# main.net
KiCad netlist of a schematic drawn in EAGLE
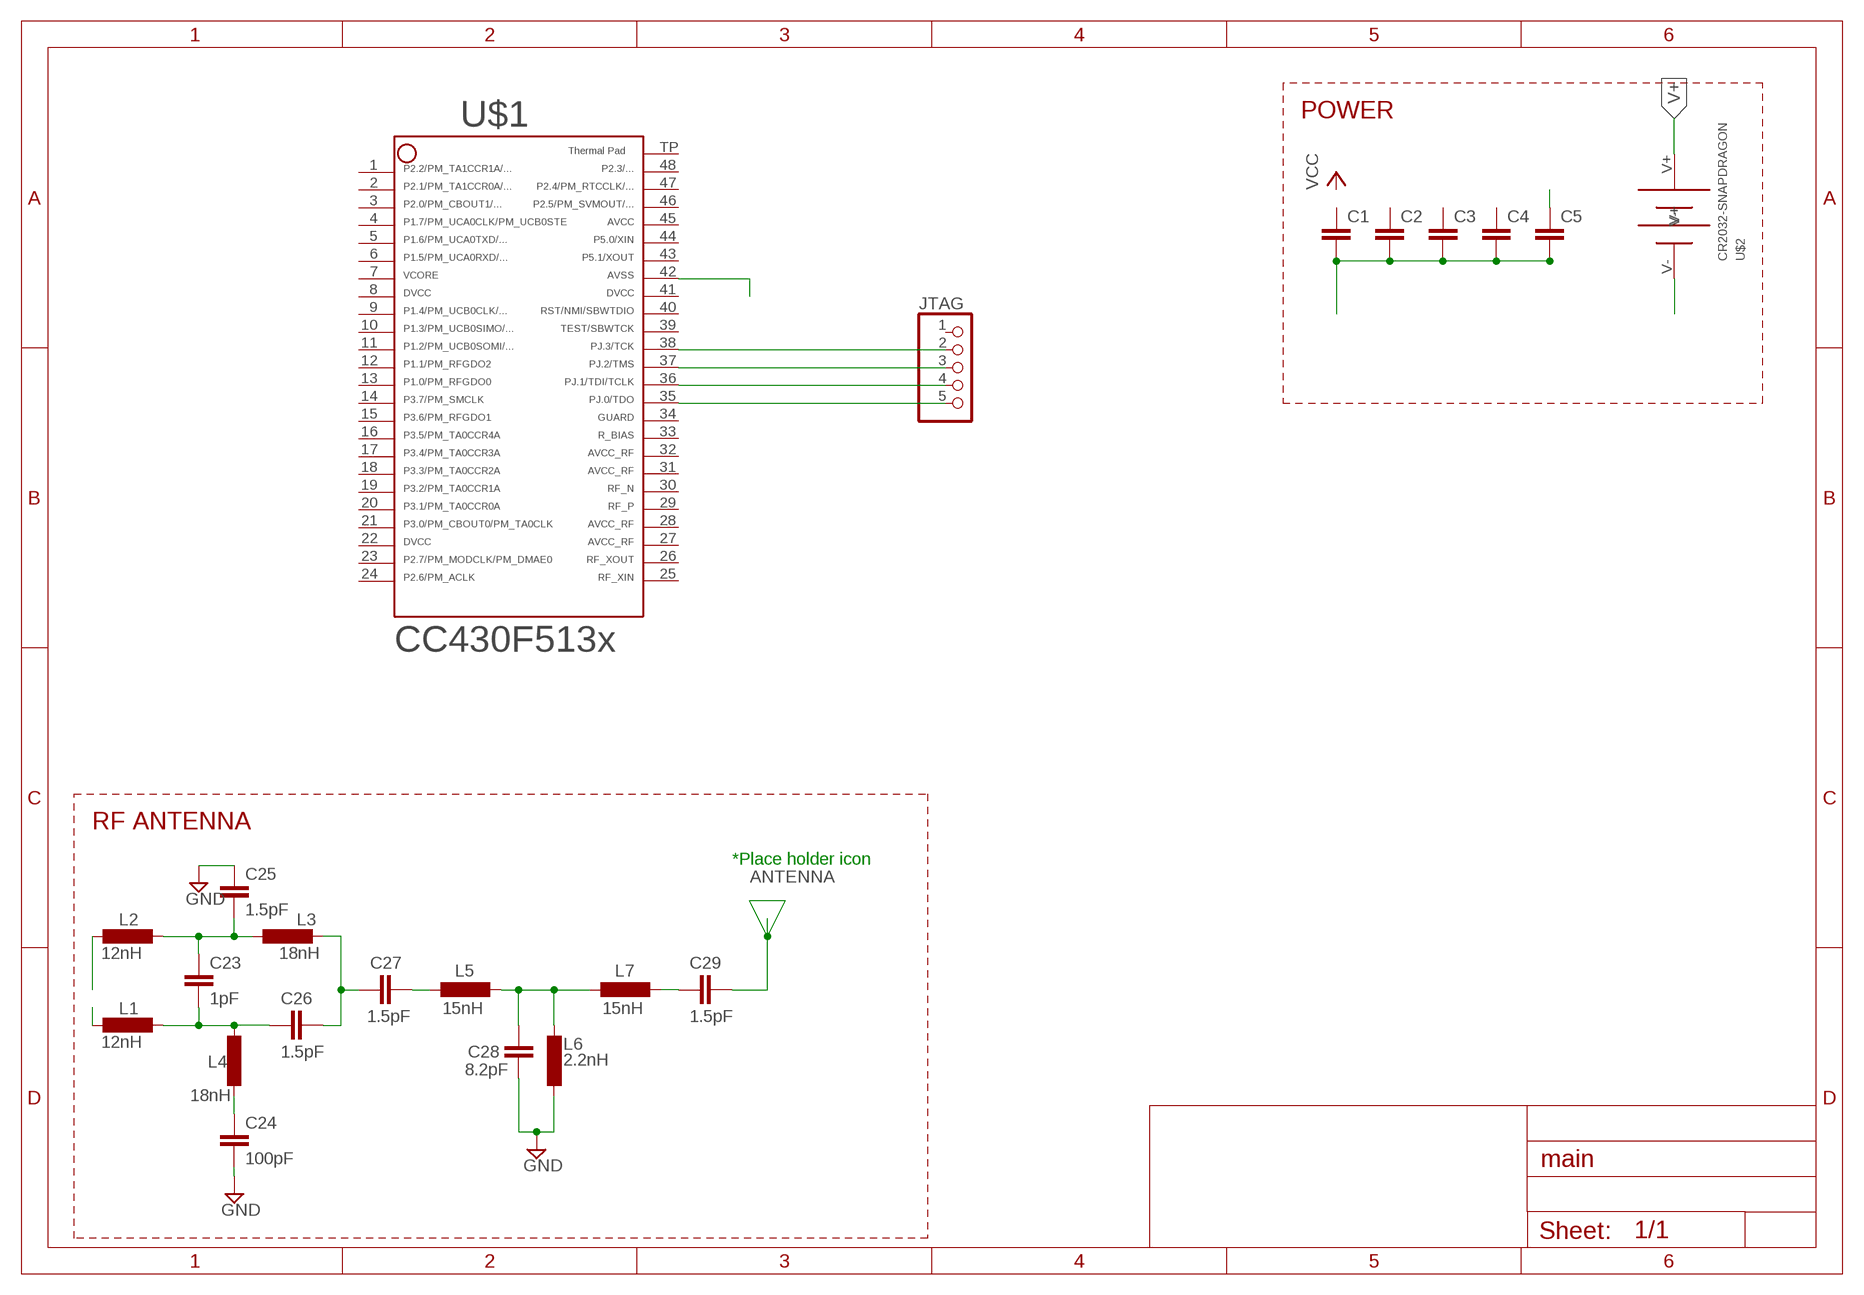
[diagram p0: schematic, sheet 1]

(export (version "E")
  (design (tool "Eeschema 10.0.6"))
  (components
    (comp (ref "C1")
      (value "C-EUC0603")
      (footprint "eagle-import:C0603")
      (libsource (lib "eagle-import") (part "C-EUC0603"))
    )
    (comp (ref "C2")
      (value "C-EUC0603")
      (footprint "eagle-import:C0603")
      (libsource (lib "eagle-import") (part "C-EUC0603"))
    )
    (comp (ref "C3")
      (value "C-EUC0603")
      (footprint "eagle-import:C0603")
      (libsource (lib "eagle-import") (part "C-EUC0603"))
    )
    (comp (ref "C4")
      (value "C-EUC0603")
      (footprint "eagle-import:C0603")
      (libsource (lib "eagle-import") (part "C-EUC0603"))
    )
    (comp (ref "C5")
      (value "C-EUC0603")
      (footprint "eagle-import:C0603")
      (libsource (lib "eagle-import") (part "C-EUC0603"))
    )
    (comp (ref "C23")
      (value "1pF")
      (footprint "eagle-import:C0603")
      (libsource (lib "eagle-import") (part "C-EUC0603"))
    )
    (comp (ref "C24")
      (value "100pF")
      (footprint "eagle-import:C0603")
      (libsource (lib "eagle-import") (part "C-EUC0603"))
    )
    (comp (ref "C25")
      (value "1.5pF")
      (footprint "eagle-import:C0603")
      (libsource (lib "eagle-import") (part "C-EUC0603"))
    )
    (comp (ref "C26")
      (value "1.5pF")
      (footprint "eagle-import:C0603")
      (libsource (lib "eagle-import") (part "C-EUC0603"))
    )
    (comp (ref "C27")
      (value "1.5pF")
      (footprint "eagle-import:C0603")
      (libsource (lib "eagle-import") (part "C-EUC0603"))
    )
    (comp (ref "C28")
      (value "8.2pF")
      (footprint "eagle-import:C0603")
      (libsource (lib "eagle-import") (part "C-EUC0603"))
    )
    (comp (ref "C29")
      (value "1.5pF")
      (footprint "eagle-import:C0603")
      (libsource (lib "eagle-import") (part "C-EUC0603"))
    )
    (comp (ref "JTAG")
      (value "PINHD-1X5")
      (footprint "eagle-import:1X05")
      (libsource (lib "eagle-import") (part "PINHD-1X5"))
    )
    (comp (ref "L1")
      (value "12nH")
      (footprint "eagle-import:L0603")
      (libsource (lib "eagle-import") (part "LL0603"))
    )
    (comp (ref "L2")
      (value "12nH")
      (footprint "eagle-import:L0603")
      (libsource (lib "eagle-import") (part "LL0603"))
    )
    (comp (ref "L3")
      (value "18nH")
      (footprint "eagle-import:L0603")
      (libsource (lib "eagle-import") (part "LL0603"))
    )
    (comp (ref "L4")
      (value "18nH")
      (footprint "eagle-import:L0603")
      (libsource (lib "eagle-import") (part "LL0603"))
    )
    (comp (ref "L5")
      (value "15nH")
      (footprint "eagle-import:L0603")
      (libsource (lib "eagle-import") (part "LL0603"))
    )
    (comp (ref "L6")
      (value "2.2nH")
      (footprint "eagle-import:L0603")
      (libsource (lib "eagle-import") (part "LL0603"))
    )
    (comp (ref "L7")
      (value "15nH")
      (footprint "eagle-import:L0603")
      (libsource (lib "eagle-import") (part "LL0603"))
    )
    (comp (ref "U$1")
      (value "CC430F513X---RGZ48")
      (footprint "eagle-import:RGZ48")
      (libsource (lib "eagle-import") (part "CC430F513X---RGZ48"))
    )
    (comp (ref "U$2")
      (value "CR2032-SNAPDRAGON")
      (footprint "eagle-import:CR2032-SNAPDRAGON")
      (libsource (lib "eagle-import") (part "CR2032-SNAPDRAGON"))
    )
  )
  (nets
    (net (code "1") (name "/7") (class "Default")
      (node (ref "U$1") (pin "7") (pinfunction "7_7") (pintype "power_in"))
    )
    (net (code "2") (name "/8") (class "Default")
      (node (ref "U$1") (pin "8") (pinfunction "8_8") (pintype "power_in"))
    )
    (net (code "3") (name "/22") (class "Default")
      (node (ref "U$1") (pin "22") (pinfunction "22_22") (pintype "power_in"))
    )
    (net (code "4") (name "/27") (class "Default")
      (node (ref "U$1") (pin "27") (pinfunction "27_27") (pintype "power_in"))
    )
    (net (code "5") (name "/31") (class "Default")
      (node (ref "U$1") (pin "31") (pinfunction "31_31") (pintype "power_in"))
    )
    (net (code "6") (name "/32") (class "Default")
      (node (ref "U$1") (pin "32") (pinfunction "32_32") (pintype "power_in"))
    )
    (net (code "7") (name "/33") (class "Default")
      (node (ref "U$1") (pin "33") (pinfunction "33_33") (pintype "power_in"))
    )
    (net (code "8") (name "/34") (class "Default")
      (node (ref "U$1") (pin "34") (pinfunction "34_34") (pintype "power_in"))
    )
    (net (code "9") (name "/41") (class "Default")
      (node (ref "U$1") (pin "41") (pinfunction "41_41") (pintype "power_in"))
    )
    (net (code "10") (name "/49") (class "Default")
      (node (ref "U$1") (pin "TP") (pinfunction "49_TP") (pintype "power_in"))
    )
    (net (code "11") (name "/ANTENNA") (class "Default")
      (node (ref "C29") (pin "1") (pinfunction "1_1") (pintype "passive"))
    )
    (net (code "12") (name "GND") (class "Default")
      (node (ref "C24") (pin "2") (pinfunction "2_2") (pintype "passive"))
      (node (ref "C25") (pin "1") (pinfunction "1_1") (pintype "passive"))
      (node (ref "C28") (pin "1") (pinfunction "1_1") (pintype "passive"))
      (node (ref "L6") (pin "2") (pinfunction "2_2") (pintype "passive"))
      (node (ref "U$2") (pin "V-") (pinfunction "V-_V-") (pintype "bidirectional"))
    )
    (net (code "13") (name "Net-(C1-Pad2)") (class "Default")
      (node (ref "C1") (pin "2") (pinfunction "2_2") (pintype "passive"))
      (node (ref "C2") (pin "2") (pinfunction "2_2") (pintype "passive"))
      (node (ref "C3") (pin "2") (pinfunction "2_2") (pintype "passive"))
      (node (ref "C4") (pin "2") (pinfunction "2_2") (pintype "passive"))
      (node (ref "C5") (pin "2") (pinfunction "2_2") (pintype "passive"))
    )
    (net (code "14") (name "Net-(C23-Pad1)") (class "Default")
      (node (ref "C23") (pin "1") (pinfunction "1_1") (pintype "passive"))
      (node (ref "C25") (pin "2") (pinfunction "2_2") (pintype "passive"))
      (node (ref "L2") (pin "1") (pinfunction "1_1") (pintype "passive"))
      (node (ref "L3") (pin "2") (pinfunction "2_2") (pintype "passive"))
    )
    (net (code "15") (name "Net-(C23-Pad2)") (class "Default")
      (node (ref "C23") (pin "2") (pinfunction "2_2") (pintype "passive"))
      (node (ref "C26") (pin "2") (pinfunction "2_2") (pintype "passive"))
      (node (ref "L1") (pin "1") (pinfunction "1_1") (pintype "passive"))
      (node (ref "L4") (pin "1") (pinfunction "1_1") (pintype "passive"))
    )
    (net (code "16") (name "Net-(C24-Pad1)") (class "Default")
      (node (ref "C24") (pin "1") (pinfunction "1_1") (pintype "passive"))
      (node (ref "L4") (pin "2") (pinfunction "2_2") (pintype "passive"))
    )
    (net (code "17") (name "Net-(C26-Pad1)") (class "Default")
      (node (ref "C26") (pin "1") (pinfunction "1_1") (pintype "passive"))
      (node (ref "C27") (pin "1") (pinfunction "1_1") (pintype "passive"))
      (node (ref "L3") (pin "1") (pinfunction "1_1") (pintype "passive"))
    )
    (net (code "18") (name "Net-(C27-Pad2)") (class "Default")
      (node (ref "C27") (pin "2") (pinfunction "2_2") (pintype "passive"))
      (node (ref "L5") (pin "1") (pinfunction "1_1") (pintype "passive"))
    )
    (net (code "19") (name "Net-(C28-Pad2)") (class "Default")
      (node (ref "C28") (pin "2") (pinfunction "2_2") (pintype "passive"))
      (node (ref "L5") (pin "2") (pinfunction "2_2") (pintype "passive"))
      (node (ref "L6") (pin "1") (pinfunction "1_1") (pintype "passive"))
      (node (ref "L7") (pin "1") (pinfunction "1_1") (pintype "passive"))
    )
    (net (code "20") (name "Net-(C29-Pad2)") (class "Default")
      (node (ref "C29") (pin "2") (pinfunction "2_2") (pintype "passive"))
      (node (ref "L7") (pin "2") (pinfunction "2_2") (pintype "passive"))
    )
    (net (code "21") (name "Net-(JTAG-Pad2)") (class "Default")
      (node (ref "JTAG") (pin "2") (pinfunction "2_2") (pintype "passive"))
      (node (ref "U$1") (pin "38") (pinfunction "38_38") (pintype "bidirectional"))
    )
    (net (code "22") (name "Net-(JTAG-Pad3)") (class "Default")
      (node (ref "JTAG") (pin "3") (pinfunction "3_3") (pintype "passive"))
      (node (ref "U$1") (pin "37") (pinfunction "37_37") (pintype "bidirectional"))
    )
    (net (code "23") (name "Net-(JTAG-Pad4)") (class "Default")
      (node (ref "JTAG") (pin "4") (pinfunction "4_4") (pintype "passive"))
      (node (ref "U$1") (pin "36") (pinfunction "36_36") (pintype "bidirectional"))
    )
    (net (code "24") (name "Net-(JTAG-Pad5)") (class "Default")
      (node (ref "JTAG") (pin "5") (pinfunction "5_5") (pintype "passive"))
      (node (ref "U$1") (pin "35") (pinfunction "35_35") (pintype "bidirectional"))
    )
    (net (code "25") (name "V+") (class "Default")
      (node (ref "U$2") (pin "V+") (pinfunction "V+_V+") (pintype "bidirectional"))
    )
    (net (code "27") (name "unconnected-(C1-Pad1)") (class "Default")
      (node (ref "C1") (pin "1") (pinfunction "1_1") (pintype "passive"))
    )
    (net (code "28") (name "unconnected-(C2-Pad1)") (class "Default")
      (node (ref "C2") (pin "1") (pinfunction "1_1") (pintype "passive"))
    )
    (net (code "29") (name "unconnected-(C3-Pad1)") (class "Default")
      (node (ref "C3") (pin "1") (pinfunction "1_1") (pintype "passive"))
    )
    (net (code "30") (name "unconnected-(C4-Pad1)") (class "Default")
      (node (ref "C4") (pin "1") (pinfunction "1_1") (pintype "passive"))
    )
    (net (code "31") (name "unconnected-(C5-Pad1)") (class "Default")
      (node (ref "C5") (pin "1") (pinfunction "1_1") (pintype "passive"))
    )
    (net (code "32") (name "unconnected-(JTAG-Pad1)") (class "Default")
      (node (ref "JTAG") (pin "1") (pinfunction "1_1") (pintype "passive"))
    )
    (net (code "33") (name "unconnected-(L1-Pad2)") (class "Default")
      (node (ref "L1") (pin "2") (pinfunction "2_2") (pintype "passive"))
    )
    (net (code "34") (name "unconnected-(L2-Pad2)") (class "Default")
      (node (ref "L2") (pin "2") (pinfunction "2_2") (pintype "passive"))
    )
    (net (code "35") (name "unconnected-(U$1-Pad1)") (class "Default")
      (node (ref "U$1") (pin "1") (pinfunction "1_1") (pintype "bidirectional"))
    )
    (net (code "36") (name "unconnected-(U$1-Pad2)") (class "Default")
      (node (ref "U$1") (pin "2") (pinfunction "2_2") (pintype "bidirectional"))
    )
    (net (code "37") (name "unconnected-(U$1-Pad3)") (class "Default")
      (node (ref "U$1") (pin "3") (pinfunction "3_3") (pintype "bidirectional"))
    )
    (net (code "38") (name "unconnected-(U$1-Pad4)") (class "Default")
      (node (ref "U$1") (pin "4") (pinfunction "4_4") (pintype "bidirectional"))
    )
    (net (code "39") (name "unconnected-(U$1-Pad5)") (class "Default")
      (node (ref "U$1") (pin "5") (pinfunction "5_5") (pintype "bidirectional"))
    )
    (net (code "40") (name "unconnected-(U$1-Pad6)") (class "Default")
      (node (ref "U$1") (pin "6") (pinfunction "6_6") (pintype "bidirectional"))
    )
    (net (code "41") (name "unconnected-(U$1-Pad9)") (class "Default")
      (node (ref "U$1") (pin "9") (pinfunction "9_9") (pintype "bidirectional"))
    )
    (net (code "42") (name "unconnected-(U$1-Pad10)") (class "Default")
      (node (ref "U$1") (pin "10") (pinfunction "10_10") (pintype "bidirectional"))
    )
    (net (code "43") (name "unconnected-(U$1-Pad11)") (class "Default")
      (node (ref "U$1") (pin "11") (pinfunction "11_11") (pintype "bidirectional"))
    )
    (net (code "44") (name "unconnected-(U$1-Pad12)") (class "Default")
      (node (ref "U$1") (pin "12") (pinfunction "12_12") (pintype "bidirectional"))
    )
    (net (code "45") (name "unconnected-(U$1-Pad13)") (class "Default")
      (node (ref "U$1") (pin "13") (pinfunction "13_13") (pintype "bidirectional"))
    )
    (net (code "46") (name "unconnected-(U$1-Pad14)") (class "Default")
      (node (ref "U$1") (pin "14") (pinfunction "14_14") (pintype "bidirectional"))
    )
    (net (code "47") (name "unconnected-(U$1-Pad15)") (class "Default")
      (node (ref "U$1") (pin "15") (pinfunction "15_15") (pintype "bidirectional"))
    )
    (net (code "48") (name "unconnected-(U$1-Pad16)") (class "Default")
      (node (ref "U$1") (pin "16") (pinfunction "16_16") (pintype "bidirectional"))
    )
    (net (code "49") (name "unconnected-(U$1-Pad17)") (class "Default")
      (node (ref "U$1") (pin "17") (pinfunction "17_17") (pintype "bidirectional"))
    )
    (net (code "50") (name "unconnected-(U$1-Pad18)") (class "Default")
      (node (ref "U$1") (pin "18") (pinfunction "18_18") (pintype "bidirectional"))
    )
    (net (code "51") (name "unconnected-(U$1-Pad19)") (class "Default")
      (node (ref "U$1") (pin "19") (pinfunction "19_19") (pintype "bidirectional"))
    )
    (net (code "52") (name "unconnected-(U$1-Pad20)") (class "Default")
      (node (ref "U$1") (pin "20") (pinfunction "20_20") (pintype "bidirectional"))
    )
    (net (code "53") (name "unconnected-(U$1-Pad21)") (class "Default")
      (node (ref "U$1") (pin "21") (pinfunction "21_21") (pintype "bidirectional"))
    )
    (net (code "54") (name "unconnected-(U$1-Pad23)") (class "Default")
      (node (ref "U$1") (pin "23") (pinfunction "23_23") (pintype "bidirectional"))
    )
    (net (code "55") (name "unconnected-(U$1-Pad24)") (class "Default")
      (node (ref "U$1") (pin "24") (pinfunction "24_24") (pintype "bidirectional"))
    )
    (net (code "56") (name "unconnected-(U$1-Pad25)") (class "Default")
      (node (ref "U$1") (pin "25") (pinfunction "25_25") (pintype "input"))
    )
    (net (code "57") (name "unconnected-(U$1-Pad26)") (class "Default")
      (node (ref "U$1") (pin "26") (pinfunction "26_26") (pintype "output"))
    )
    (net (code "58") (name "unconnected-(U$1-Pad28)") (class "Default")
      (node (ref "U$1") (pin "28") (pinfunction "28_28") (pintype "bidirectional"))
    )
    (net (code "59") (name "unconnected-(U$1-Pad29)") (class "Default")
      (node (ref "U$1") (pin "29") (pinfunction "29_29") (pintype "bidirectional"))
    )
    (net (code "60") (name "unconnected-(U$1-Pad30)") (class "Default")
      (node (ref "U$1") (pin "30") (pinfunction "30_30") (pintype "bidirectional"))
    )
    (net (code "61") (name "unconnected-(U$1-Pad39)") (class "Default")
      (node (ref "U$1") (pin "39") (pinfunction "39_39") (pintype "input"))
    )
    (net (code "62") (name "unconnected-(U$1-Pad40)") (class "Default")
      (node (ref "U$1") (pin "40") (pinfunction "40_40") (pintype "bidirectional"))
    )
    (net (code "63") (name "unconnected-(U$1-Pad42)") (class "Default")
      (node (ref "U$1") (pin "42") (pinfunction "42_42") (pintype "power_in"))
    )
    (net (code "64") (name "unconnected-(U$1-Pad43)") (class "Default")
      (node (ref "U$1") (pin "43") (pinfunction "43_43") (pintype "input"))
    )
    (net (code "65") (name "unconnected-(U$1-Pad44)") (class "Default")
      (node (ref "U$1") (pin "44") (pinfunction "44_44") (pintype "input"))
    )
    (net (code "66") (name "unconnected-(U$1-Pad45)") (class "Default")
      (node (ref "U$1") (pin "45") (pinfunction "45_45") (pintype "input"))
    )
    (net (code "67") (name "unconnected-(U$1-Pad46)") (class "Default")
      (node (ref "U$1") (pin "46") (pinfunction "46_46") (pintype "bidirectional"))
    )
    (net (code "68") (name "unconnected-(U$1-Pad47)") (class "Default")
      (node (ref "U$1") (pin "47") (pinfunction "47_47") (pintype "input"))
    )
    (net (code "69") (name "unconnected-(U$1-Pad48)") (class "Default")
      (node (ref "U$1") (pin "48") (pinfunction "48_48") (pintype "bidirectional"))
    )
  )
)
